# 08-AUDIO_OUTER.net
KiCad netlist of a schematic drawn in Altium Designer
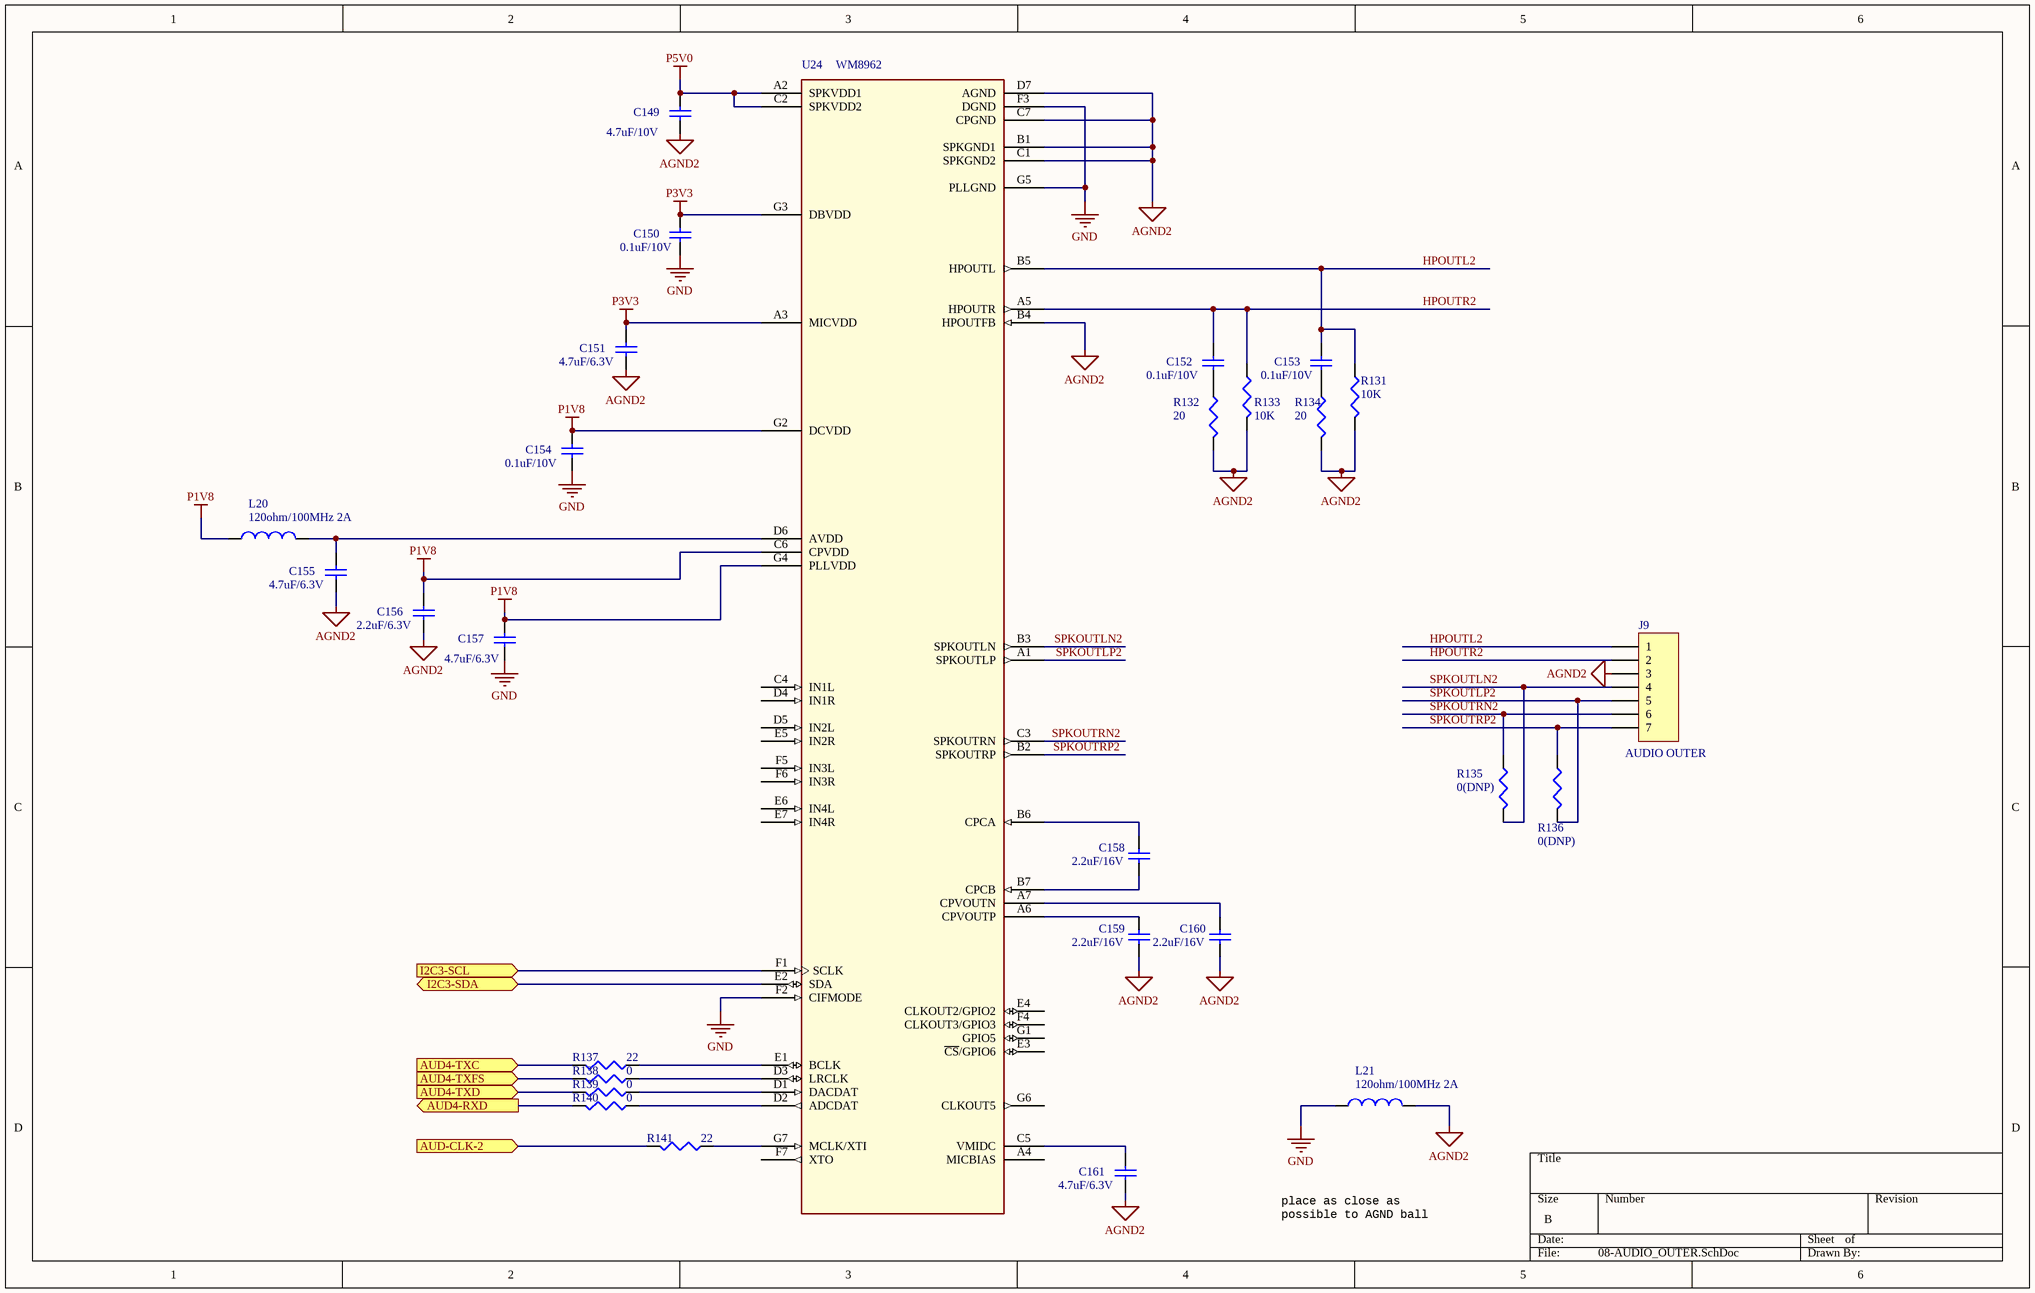
[diagram p0: 08-AUDIO_OUTER.SchDoc]

(export (version "E")
  (design (tool "Eeschema 10.0.6"))
  (components
    (comp (ref "C149")
      (value "4.7uF/10V")
      (footprint "0805")
      (description "Capacitor")
      (fields (field (name "PUBLISHER") "Altium Limited"))
      (libsource (lib "Miscellaneous Devices") (part "Cap"))
    )
    (comp (ref "C150")
      (value "0.1uF/10V")
      (footprint "0402")
      (description "Capacitor")
      (fields (field (name "PUBLISHER") "Altium Limited"))
      (libsource (lib "Miscellaneous Devices") (part "Cap"))
    )
    (comp (ref "C151")
      (value "4.7uF/6.3V")
      (footprint "0603")
      (description "Capacitor")
      (fields (field (name "PUBLISHER") "Altium Limited"))
      (libsource (lib "Miscellaneous Devices") (part "Cap"))
    )
    (comp (ref "C152")
      (value "0.1uF/10V")
      (footprint "0402")
      (description "Capacitor")
      (fields (field (name "PUBLISHER") "Altium Limited"))
      (libsource (lib "Miscellaneous Devices") (part "Cap"))
    )
    (comp (ref "C153")
      (value "0.1uF/10V")
      (footprint "0402")
      (description "Capacitor")
      (fields (field (name "PUBLISHER") "Altium Limited"))
      (libsource (lib "Miscellaneous Devices") (part "Cap"))
    )
    (comp (ref "C154")
      (value "0.1uF/10V")
      (footprint "0402")
      (description "Capacitor")
      (fields (field (name "PUBLISHER") "Altium Limited"))
      (libsource (lib "Miscellaneous Devices") (part "Cap"))
    )
    (comp (ref "C155")
      (value "4.7uF/6.3V")
      (footprint "0603")
      (description "Capacitor")
      (fields (field (name "PUBLISHER") "Altium Limited"))
      (libsource (lib "Miscellaneous Devices") (part "Cap"))
    )
    (comp (ref "C156")
      (value "2.2uF/6.3V")
      (footprint "0603")
      (description "Capacitor")
      (fields (field (name "PUBLISHER") "Altium Limited"))
      (libsource (lib "Miscellaneous Devices") (part "Cap"))
    )
    (comp (ref "C157")
      (value "4.7uF/6.3V")
      (footprint "0603")
      (description "Capacitor")
      (fields (field (name "PUBLISHER") "Altium Limited"))
      (libsource (lib "Miscellaneous Devices") (part "Cap"))
    )
    (comp (ref "C158")
      (value "2.2uF/16V")
      (footprint "0603")
      (description "Capacitor")
      (fields (field (name "PUBLISHER") "Altium Limited"))
      (libsource (lib "Miscellaneous Devices") (part "Cap"))
    )
    (comp (ref "C159")
      (value "2.2uF/16V")
      (footprint "0603")
      (description "Capacitor")
      (fields (field (name "PUBLISHER") "Altium Limited"))
      (libsource (lib "Miscellaneous Devices") (part "Cap"))
    )
    (comp (ref "C160")
      (value "2.2uF/16V")
      (footprint "0603")
      (description "Capacitor")
      (fields (field (name "PUBLISHER") "Altium Limited"))
      (libsource (lib "Miscellaneous Devices") (part "Cap"))
    )
    (comp (ref "C161")
      (value "4.7uF/6.3V")
      (footprint "0603")
      (description "Capacitor")
      (fields (field (name "PUBLISHER") "Altium Limited"))
      (libsource (lib "Miscellaneous Devices") (part "Cap"))
    )
    (comp (ref "J9")
      (value "AUDIO OUTER")
      (footprint "CON-7PIN")
      (description "Header, 7-Pin")
      (fields (field (name "PUBLISHER") "Altium Limited"))
      (libsource (lib "Miscellaneous Connectors") (part "Header 7"))
    )
    (comp (ref "L20")
      (value "120ohm/100MHz 2A")
      (footprint "0603")
      (description "Inductor")
      (fields (field (name "PUBLISHER") "Altium Limited"))
      (libsource (lib "Miscellaneous Devices") (part "Inductor"))
    )
    (comp (ref "L21")
      (value "120ohm/100MHz 2A")
      (footprint "0603")
      (description "Inductor")
      (fields (field (name "PUBLISHER") "Altium Limited"))
      (libsource (lib "Miscellaneous Devices") (part "Inductor"))
    )
    (comp (ref "R131") (value "10K") (footprint "0402") (libsource (lib "*") (part "CR16-1003FM")))
    (comp (ref "R132") (value "20") (footprint "0402") (libsource (lib "*") (part "CR16-1003FM")))
    (comp (ref "R133") (value "10K") (footprint "0402") (libsource (lib "*") (part "CR16-1003FM")))
    (comp (ref "R134") (value "20") (footprint "0402") (libsource (lib "*") (part "CR16-1003FM")))
    (comp (ref "R135") (value "0(DNP)") (footprint "0603") (libsource (lib "*") (part "CR16-1003FM")))
    (comp (ref "R136") (value "0(DNP)") (footprint "0603") (libsource (lib "*") (part "CR16-1003FM")))
    (comp (ref "R137") (value "22") (footprint "0402") (libsource (lib "*") (part "CR16-1003FM")))
    (comp (ref "R138") (value "0") (footprint "0402") (libsource (lib "*") (part "CR16-1003FM")))
    (comp (ref "R139") (value "0") (footprint "0402") (libsource (lib "*") (part "CR16-1003FM")))
    (comp (ref "R140") (value "0") (footprint "0402") (libsource (lib "*") (part "CR16-1003FM")))
    (comp (ref "R141") (value "22") (footprint "0402") (libsource (lib "*") (part "CR16-1003FM")))
    (comp (ref "U24")
      (value "WM8962")
      (footprint "BGA49")
      (description "IC AUDIO CODEC 24BIT DAC 2 CH ADC 1.8V BGA49")
      (libsource (lib "*") (part "WM8962_BGA_49P_CUST"))
    )
  )
  (nets
    (net (code "1") (name "/AUD-CLK-2") (class "Default")
      (node (ref "R141") (pin "2") (pinfunction "2_2") (pintype "passive"))
    )
    (net (code "2") (name "/AUD4-RXD") (class "Default")
      (node (ref "R140") (pin "2") (pinfunction "2_2") (pintype "passive"))
    )
    (net (code "3") (name "/AUD4-TXC") (class "Default")
      (node (ref "R137") (pin "2") (pinfunction "2_2") (pintype "passive"))
    )
    (net (code "4") (name "/AUD4-TXD") (class "Default")
      (node (ref "R139") (pin "2") (pinfunction "2_2") (pintype "passive"))
    )
    (net (code "5") (name "/AUD4-TXFS") (class "Default")
      (node (ref "R138") (pin "2") (pinfunction "2_2") (pintype "passive"))
    )
    (net (code "6") (name "/HPOUTL2") (class "Default")
      (node (ref "C153") (pin "2") (pinfunction "2_2") (pintype "passive"))
      (node (ref "J9") (pin "1") (pinfunction "1_1") (pintype "passive"))
      (node (ref "R131") (pin "1") (pinfunction "1_1") (pintype "passive"))
      (node (ref "U24") (pin "B5") (pinfunction "HPOUTL_B5") (pintype "output"))
    )
    (net (code "7") (name "/HPOUTR2") (class "Default")
      (node (ref "C152") (pin "2") (pinfunction "2_2") (pintype "passive"))
      (node (ref "J9") (pin "2") (pinfunction "2_2") (pintype "passive"))
      (node (ref "R133") (pin "1") (pinfunction "1_1") (pintype "passive"))
      (node (ref "U24") (pin "A5") (pinfunction "HPOUTR_A5") (pintype "output"))
    )
    (net (code "8") (name "/I2C3-SCL") (class "Default")
      (node (ref "U24") (pin "F1") (pinfunction "SCLK_F1") (pintype "input"))
    )
    (net (code "9") (name "/I2C3-SDA") (class "Default")
      (node (ref "U24") (pin "E2") (pinfunction "SDA_E2") (pintype "bidirectional"))
    )
    (net (code "10") (name "/SPKOUTLN2") (class "Default")
      (node (ref "J9") (pin "4") (pinfunction "4_4") (pintype "passive"))
      (node (ref "R135") (pin "2") (pinfunction "2_2") (pintype "passive"))
      (node (ref "U24") (pin "B3") (pinfunction "SPKOUTLN_B3") (pintype "output"))
    )
    (net (code "11") (name "/SPKOUTLP2") (class "Default")
      (node (ref "J9") (pin "5") (pinfunction "5_5") (pintype "passive"))
      (node (ref "R136") (pin "2") (pinfunction "2_2") (pintype "passive"))
      (node (ref "U24") (pin "A1") (pinfunction "SPKOUTLP_A1") (pintype "output"))
    )
    (net (code "12") (name "/SPKOUTRN2") (class "Default")
      (node (ref "J9") (pin "6") (pinfunction "6_6") (pintype "passive"))
      (node (ref "R135") (pin "1") (pinfunction "1_1") (pintype "passive"))
      (node (ref "U24") (pin "C3") (pinfunction "SPKOUTRN_C3") (pintype "output"))
    )
    (net (code "13") (name "/SPKOUTRP2") (class "Default")
      (node (ref "J9") (pin "7") (pinfunction "7_7") (pintype "passive"))
      (node (ref "R136") (pin "1") (pinfunction "1_1") (pintype "passive"))
      (node (ref "U24") (pin "B2") (pinfunction "SPKOUTRP_B2") (pintype "output"))
    )
    (net (code "14") (name "AGND2") (class "Default")
      (node (ref "C149") (pin "1") (pinfunction "1_1") (pintype "passive"))
      (node (ref "C151") (pin "1") (pinfunction "1_1") (pintype "passive"))
      (node (ref "C155") (pin "1") (pinfunction "1_1") (pintype "passive"))
      (node (ref "C156") (pin "1") (pinfunction "1_1") (pintype "passive"))
      (node (ref "C159") (pin "1") (pinfunction "1_1") (pintype "passive"))
      (node (ref "C160") (pin "1") (pinfunction "1_1") (pintype "passive"))
      (node (ref "C161") (pin "1") (pinfunction "1_1") (pintype "passive"))
      (node (ref "J9") (pin "3") (pinfunction "3_3") (pintype "passive"))
      (node (ref "L21") (pin "2") (pinfunction "2_2") (pintype "passive"))
      (node (ref "R131") (pin "2") (pinfunction "2_2") (pintype "passive"))
      (node (ref "R132") (pin "2") (pinfunction "2_2") (pintype "passive"))
      (node (ref "R133") (pin "2") (pinfunction "2_2") (pintype "passive"))
      (node (ref "R134") (pin "2") (pinfunction "2_2") (pintype "passive"))
      (node (ref "U24") (pin "B1") (pinfunction "SPKGND1_B1") (pintype "power_in"))
      (node (ref "U24") (pin "B4") (pinfunction "HPOUTFB_B4") (pintype "input"))
      (node (ref "U24") (pin "C1") (pinfunction "SPKGND2_C1") (pintype "power_in"))
      (node (ref "U24") (pin "C7") (pinfunction "CPGND_C7") (pintype "power_in"))
      (node (ref "U24") (pin "D7") (pinfunction "AGND_D7") (pintype "power_in"))
    )
    (net (code "15") (name "GND") (class "Default")
      (node (ref "C150") (pin "1") (pinfunction "1_1") (pintype "passive"))
      (node (ref "C154") (pin "1") (pinfunction "1_1") (pintype "passive"))
      (node (ref "C157") (pin "1") (pinfunction "1_1") (pintype "passive"))
      (node (ref "L21") (pin "1") (pinfunction "1_1") (pintype "passive"))
      (node (ref "U24") (pin "F2") (pinfunction "CIFMODE_F2") (pintype "input"))
      (node (ref "U24") (pin "F3") (pinfunction "DGND_F3") (pintype "power_in"))
      (node (ref "U24") (pin "G5") (pinfunction "PLLGND_G5") (pintype "power_in"))
    )
    (net (code "16") (name "Net-(C152-Pad1)") (class "Default")
      (node (ref "C152") (pin "1") (pinfunction "1_1") (pintype "passive"))
      (node (ref "R132") (pin "1") (pinfunction "1_1") (pintype "passive"))
    )
    (net (code "17") (name "Net-(C153-Pad1)") (class "Default")
      (node (ref "C153") (pin "1") (pinfunction "1_1") (pintype "passive"))
      (node (ref "R134") (pin "1") (pinfunction "1_1") (pintype "passive"))
    )
    (net (code "18") (name "Net-(U24-ADCDAT)") (class "Default")
      (node (ref "R140") (pin "1") (pinfunction "1_1") (pintype "passive"))
      (node (ref "U24") (pin "D2") (pinfunction "ADCDAT_D2") (pintype "output"))
    )
    (net (code "19") (name "Net-(U24-AVDD)") (class "Default")
      (node (ref "C155") (pin "2") (pinfunction "2_2") (pintype "passive"))
      (node (ref "L20") (pin "2") (pinfunction "2_2") (pintype "passive"))
      (node (ref "U24") (pin "D6") (pinfunction "AVDD_D6") (pintype "power_in"))
    )
    (net (code "20") (name "Net-(U24-BCLK)") (class "Default")
      (node (ref "R137") (pin "1") (pinfunction "1_1") (pintype "passive"))
      (node (ref "U24") (pin "E1") (pinfunction "BCLK_E1") (pintype "bidirectional"))
    )
    (net (code "21") (name "Net-(U24-CPCA)") (class "Default")
      (node (ref "C158") (pin "2") (pinfunction "2_2") (pintype "passive"))
      (node (ref "U24") (pin "B6") (pinfunction "CPCA_B6") (pintype "input"))
    )
    (net (code "22") (name "Net-(U24-CPCB)") (class "Default")
      (node (ref "C158") (pin "1") (pinfunction "1_1") (pintype "passive"))
      (node (ref "U24") (pin "B7") (pinfunction "CPCB_B7") (pintype "input"))
    )
    (net (code "23") (name "Net-(U24-CPVOUTN)") (class "Default")
      (node (ref "C160") (pin "2") (pinfunction "2_2") (pintype "passive"))
      (node (ref "U24") (pin "A7") (pinfunction "CPVOUTN_A7") (pintype "power_in"))
    )
    (net (code "24") (name "Net-(U24-CPVOUTP)") (class "Default")
      (node (ref "C159") (pin "2") (pinfunction "2_2") (pintype "passive"))
      (node (ref "U24") (pin "A6") (pinfunction "CPVOUTP_A6") (pintype "power_in"))
    )
    (net (code "25") (name "Net-(U24-DACDAT)") (class "Default")
      (node (ref "R139") (pin "1") (pinfunction "1_1") (pintype "passive"))
      (node (ref "U24") (pin "D1") (pinfunction "DACDAT_D1") (pintype "input"))
    )
    (net (code "26") (name "Net-(U24-LRCLK)") (class "Default")
      (node (ref "R138") (pin "1") (pinfunction "1_1") (pintype "passive"))
      (node (ref "U24") (pin "D3") (pinfunction "LRCLK_D3") (pintype "bidirectional"))
    )
    (net (code "27") (name "Net-(U24-MCLK{slash}XTI)") (class "Default")
      (node (ref "R141") (pin "1") (pinfunction "1_1") (pintype "passive"))
      (node (ref "U24") (pin "G7") (pinfunction "MCLK/XTI_G7") (pintype "input"))
    )
    (net (code "28") (name "Net-(U24-VMIDC)") (class "Default")
      (node (ref "C161") (pin "2") (pinfunction "2_2") (pintype "passive"))
      (node (ref "U24") (pin "C5") (pinfunction "VMIDC_C5") (pintype "power_in"))
    )
    (net (code "29") (name "P1V8") (class "Default")
      (node (ref "C154") (pin "2") (pinfunction "2_2") (pintype "passive"))
      (node (ref "C156") (pin "2") (pinfunction "2_2") (pintype "passive"))
      (node (ref "C157") (pin "2") (pinfunction "2_2") (pintype "passive"))
      (node (ref "L20") (pin "1") (pinfunction "1_1") (pintype "passive"))
      (node (ref "U24") (pin "C6") (pinfunction "CPVDD_C6") (pintype "power_in"))
      (node (ref "U24") (pin "G2") (pinfunction "DCVDD_G2") (pintype "power_in"))
      (node (ref "U24") (pin "G4") (pinfunction "PLLVDD_G4") (pintype "power_in"))
    )
    (net (code "30") (name "P3V3") (class "Default")
      (node (ref "C150") (pin "2") (pinfunction "2_2") (pintype "passive"))
      (node (ref "C151") (pin "2") (pinfunction "2_2") (pintype "passive"))
      (node (ref "U24") (pin "A3") (pinfunction "MICVDD_A3") (pintype "power_in"))
      (node (ref "U24") (pin "G3") (pinfunction "DBVDD_G3") (pintype "power_in"))
    )
    (net (code "31") (name "P5V0") (class "Default")
      (node (ref "C149") (pin "2") (pinfunction "2_2") (pintype "passive"))
      (node (ref "U24") (pin "A2") (pinfunction "SPKVDD1_A2") (pintype "power_in"))
      (node (ref "U24") (pin "C2") (pinfunction "SPKVDD2_C2") (pintype "power_in"))
    )
    (net (code "32") (name "unconnected-(U24-CLKOUT2{slash}GPIO2-PadE4)") (class "Default")
      (node (ref "U24") (pin "E4") (pinfunction "CLKOUT2/GPIO2_E4") (pintype "bidirectional"))
    )
    (net (code "33") (name "unconnected-(U24-CLKOUT3{slash}GPIO3-PadF4)") (class "Default")
      (node (ref "U24") (pin "F4") (pinfunction "CLKOUT3/GPIO3_F4") (pintype "bidirectional"))
    )
    (net (code "34") (name "unconnected-(U24-CLKOUT5-PadG6)") (class "Default")
      (node (ref "U24") (pin "G6") (pinfunction "CLKOUT5_G6") (pintype "output"))
    )
    (net (code "35") (name "unconnected-(U24-GPIO5-PadG1)") (class "Default")
      (node (ref "U24") (pin "G1") (pinfunction "GPIO5_G1") (pintype "bidirectional"))
    )
    (net (code "36") (name "unconnected-(U24-IN1L-PadC4)") (class "Default")
      (node (ref "U24") (pin "C4") (pinfunction "IN1L_C4") (pintype "input"))
    )
    (net (code "37") (name "unconnected-(U24-IN1R-PadD4)") (class "Default")
      (node (ref "U24") (pin "D4") (pinfunction "IN1R_D4") (pintype "input"))
    )
    (net (code "38") (name "unconnected-(U24-IN2L-PadD5)") (class "Default")
      (node (ref "U24") (pin "D5") (pinfunction "IN2L_D5") (pintype "input"))
    )
    (net (code "39") (name "unconnected-(U24-IN2R-PadE5)") (class "Default")
      (node (ref "U24") (pin "E5") (pinfunction "IN2R_E5") (pintype "input"))
    )
    (net (code "40") (name "unconnected-(U24-IN3L-PadF5)") (class "Default")
      (node (ref "U24") (pin "F5") (pinfunction "IN3L_F5") (pintype "input"))
    )
    (net (code "41") (name "unconnected-(U24-IN3R-PadF6)") (class "Default")
      (node (ref "U24") (pin "F6") (pinfunction "IN3R_F6") (pintype "input"))
    )
    (net (code "42") (name "unconnected-(U24-IN4L-PadE6)") (class "Default")
      (node (ref "U24") (pin "E6") (pinfunction "IN4L_E6") (pintype "input"))
    )
    (net (code "43") (name "unconnected-(U24-IN4R-PadE7)") (class "Default")
      (node (ref "U24") (pin "E7") (pinfunction "IN4R_E7") (pintype "input"))
    )
    (net (code "44") (name "unconnected-(U24-MICBIAS-PadA4)") (class "Default")
      (node (ref "U24") (pin "A4") (pinfunction "MICBIAS_A4") (pintype "passive"))
    )
    (net (code "45") (name "unconnected-(U24-XTO-PadF7)") (class "Default")
      (node (ref "U24") (pin "F7") (pinfunction "XTO_F7") (pintype "output"))
    )
    (net (code "46") (name "unconnected-(U24-~{CS}{slash}GPIO6-PadE3)") (class "Default")
      (node (ref "U24") (pin "E3") (pinfunction "~{CS}/GPIO6_E3") (pintype "bidirectional"))
    )
  )
)
